# cpu1_gsm_module.net
KiCad netlist of a schematic drawn in Altium Designer
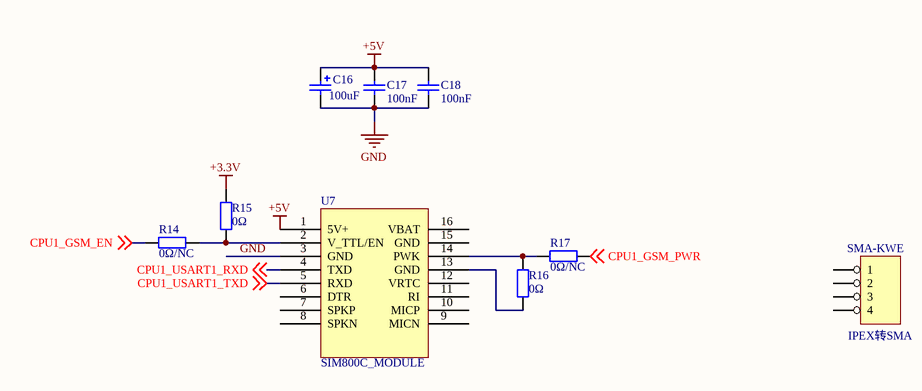
[diagram p0: cpu1_gsm_module.SchDoc]

(export (version "E")
  (design (tool "Eeschema 10.0.6"))
  (components
    (comp (ref "C16")
      (value "100uF")
      (footprint "CASE-B_3528")
      (description "钽电容")
      (libsource (lib "Miscellaneous Devices LC") (part "3528 100uF (107) 10% 6.3V"))
    )
    (comp (ref "C17")
      (value "100nF")
      (footprint "0805_C")
      (description "贴片电容")
      (libsource (lib "Miscellaneous Devices LC") (part "0805 100nF(104) 10% 50V"))
    )
    (comp (ref "C18")
      (value "100nF")
      (footprint "0805_C")
      (description "贴片电容")
      (libsource (lib "Miscellaneous Devices LC") (part "0805 100nF(104) 10% 50V"))
    )
    (comp (ref "R14")
      (value "0Ω/NC")
      (footprint "0805_R")
      (description "贴片电阻")
      (libsource (lib "") (part "0805 11KΩ (1102) 1%_2"))
    )
    (comp (ref "R15")
      (value "0Ω")
      (footprint "0805_R")
      (description "贴片电阻")
      (libsource (lib "") (part "0805 11KΩ (1102) 1%_1"))
    )
    (comp (ref "R16")
      (value "0Ω")
      (footprint "0805_R")
      (description "贴片电阻")
      (libsource (lib "Miscellaneous Devices LC") (part "0805 11KΩ (1102) 1%"))
    )
    (comp (ref "R17")
      (value "0Ω/NC")
      (footprint "0805_R")
      (description "贴片电阻")
      (libsource (lib "") (part "0805 11KΩ (1102) 1%_2"))
    )
    (comp (ref "SMA-KWE")
      (value "4 HEADER")
      (footprint "SMA-KWE")
      (description "4 Pin Header")
      (libsource (lib "myIntegrated_Library1") (part "4 HEADER"))
    )
    (comp (ref "U7")
      (value "SIM800C_MODULE")
      (footprint "SIM800C_MODULE")
      (libsource (lib "myIntegrated_Library1") (part "SIM800C_MODULE"))
    )
  )
  (nets
    (net (code "1") (name "+3.3V") (class "Default")
      (node (ref "R15") (pin "2") (pinfunction "2_2") (pintype "passive"))
    )
    (net (code "2") (name "+5V") (class "Default")
      (node (ref "C16") (pin "1") (pinfunction "1_1") (pintype "passive"))
      (node (ref "C17") (pin "2") (pinfunction "2_2") (pintype "passive"))
      (node (ref "C18") (pin "2") (pinfunction "2_2") (pintype "passive"))
      (node (ref "U7") (pin "1") (pinfunction "5V+_1") (pintype "passive"))
    )
    (net (code "3") (name "CPU1_GSM_EN") (class "Default")
      (node (ref "R14") (pin "2") (pinfunction "2_2") (pintype "passive"))
    )
    (net (code "4") (name "CPU1_GSM_PWR") (class "Default")
      (node (ref "R17") (pin "1") (pinfunction "1_1") (pintype "passive"))
    )
    (net (code "5") (name "CPU1_USART1_RXD") (class "Default")
      (node (ref "U7") (pin "4") (pinfunction "TXD_4") (pintype "passive"))
    )
    (net (code "6") (name "CPU1_USART1_TXD") (class "Default")
      (node (ref "U7") (pin "5") (pinfunction "RXD_5") (pintype "passive"))
    )
    (net (code "7") (name "GND") (class "Default")
      (node (ref "C16") (pin "2") (pinfunction "2_2") (pintype "passive"))
      (node (ref "C17") (pin "1") (pinfunction "1_1") (pintype "passive"))
      (node (ref "C18") (pin "1") (pinfunction "1_1") (pintype "passive"))
      (node (ref "U7") (pin "3") (pinfunction "GND_3") (pintype "passive"))
    )
    (net (code "8") (name "Net-(R16-Pad2)") (class "Default")
      (node (ref "R16") (pin "2") (pinfunction "2_2") (pintype "passive"))
      (node (ref "U7") (pin "13") (pinfunction "GND_13") (pintype "passive"))
    )
    (net (code "9") (name "Net-(U7-PWK)") (class "Default")
      (node (ref "R16") (pin "1") (pinfunction "1_1") (pintype "passive"))
      (node (ref "R17") (pin "2") (pinfunction "2_2") (pintype "passive"))
      (node (ref "U7") (pin "14") (pinfunction "PWK_14") (pintype "passive"))
    )
    (net (code "10") (name "Net-(U7-V_TTL{slash}EN)") (class "Default")
      (node (ref "R14") (pin "1") (pinfunction "1_1") (pintype "passive"))
      (node (ref "R15") (pin "1") (pinfunction "1_1") (pintype "passive"))
      (node (ref "U7") (pin "2") (pinfunction "V_TTL/EN_2") (pintype "passive"))
    )
    (net (code "11") (name "unconnected-(SMA-KWE-Pad1)") (class "Default")
      (node (ref "SMA-KWE") (pin "1") (pinfunction "1_1") (pintype "passive"))
    )
    (net (code "12") (name "unconnected-(SMA-KWE-Pad2)") (class "Default")
      (node (ref "SMA-KWE") (pin "2") (pinfunction "2_2") (pintype "passive"))
    )
    (net (code "13") (name "unconnected-(SMA-KWE-Pad3)") (class "Default")
      (node (ref "SMA-KWE") (pin "3") (pinfunction "3_3") (pintype "passive"))
    )
    (net (code "14") (name "unconnected-(SMA-KWE-Pad4)") (class "Default")
      (node (ref "SMA-KWE") (pin "4") (pinfunction "4_4") (pintype "passive"))
    )
    (net (code "15") (name "unconnected-(U7-DTR-Pad6)") (class "Default")
      (node (ref "U7") (pin "6") (pinfunction "DTR_6") (pintype "passive"))
    )
    (net (code "16") (name "unconnected-(U7-GND-Pad15)") (class "Default")
      (node (ref "U7") (pin "15") (pinfunction "GND_15") (pintype "passive"))
    )
    (net (code "17") (name "unconnected-(U7-MICN-Pad9)") (class "Default")
      (node (ref "U7") (pin "9") (pinfunction "MICN_9") (pintype "passive"))
    )
    (net (code "18") (name "unconnected-(U7-MICP-Pad10)") (class "Default")
      (node (ref "U7") (pin "10") (pinfunction "MICP_10") (pintype "passive"))
    )
    (net (code "19") (name "unconnected-(U7-RI-Pad11)") (class "Default")
      (node (ref "U7") (pin "11") (pinfunction "RI_11") (pintype "passive"))
    )
    (net (code "20") (name "unconnected-(U7-SPKN-Pad8)") (class "Default")
      (node (ref "U7") (pin "8") (pinfunction "SPKN_8") (pintype "passive"))
    )
    (net (code "21") (name "unconnected-(U7-SPKP-Pad7)") (class "Default")
      (node (ref "U7") (pin "7") (pinfunction "SPKP_7") (pintype "passive"))
    )
    (net (code "22") (name "unconnected-(U7-VBAT-Pad16)") (class "Default")
      (node (ref "U7") (pin "16") (pinfunction "VBAT_16") (pintype "passive"))
    )
    (net (code "23") (name "unconnected-(U7-VRTC-Pad12)") (class "Default")
      (node (ref "U7") (pin "12") (pinfunction "VRTC_12") (pintype "passive"))
    )
  )
)
